# helmet_blinker_light_ACY_v0_1.net
KiCad netlist of a schematic drawn in EAGLE
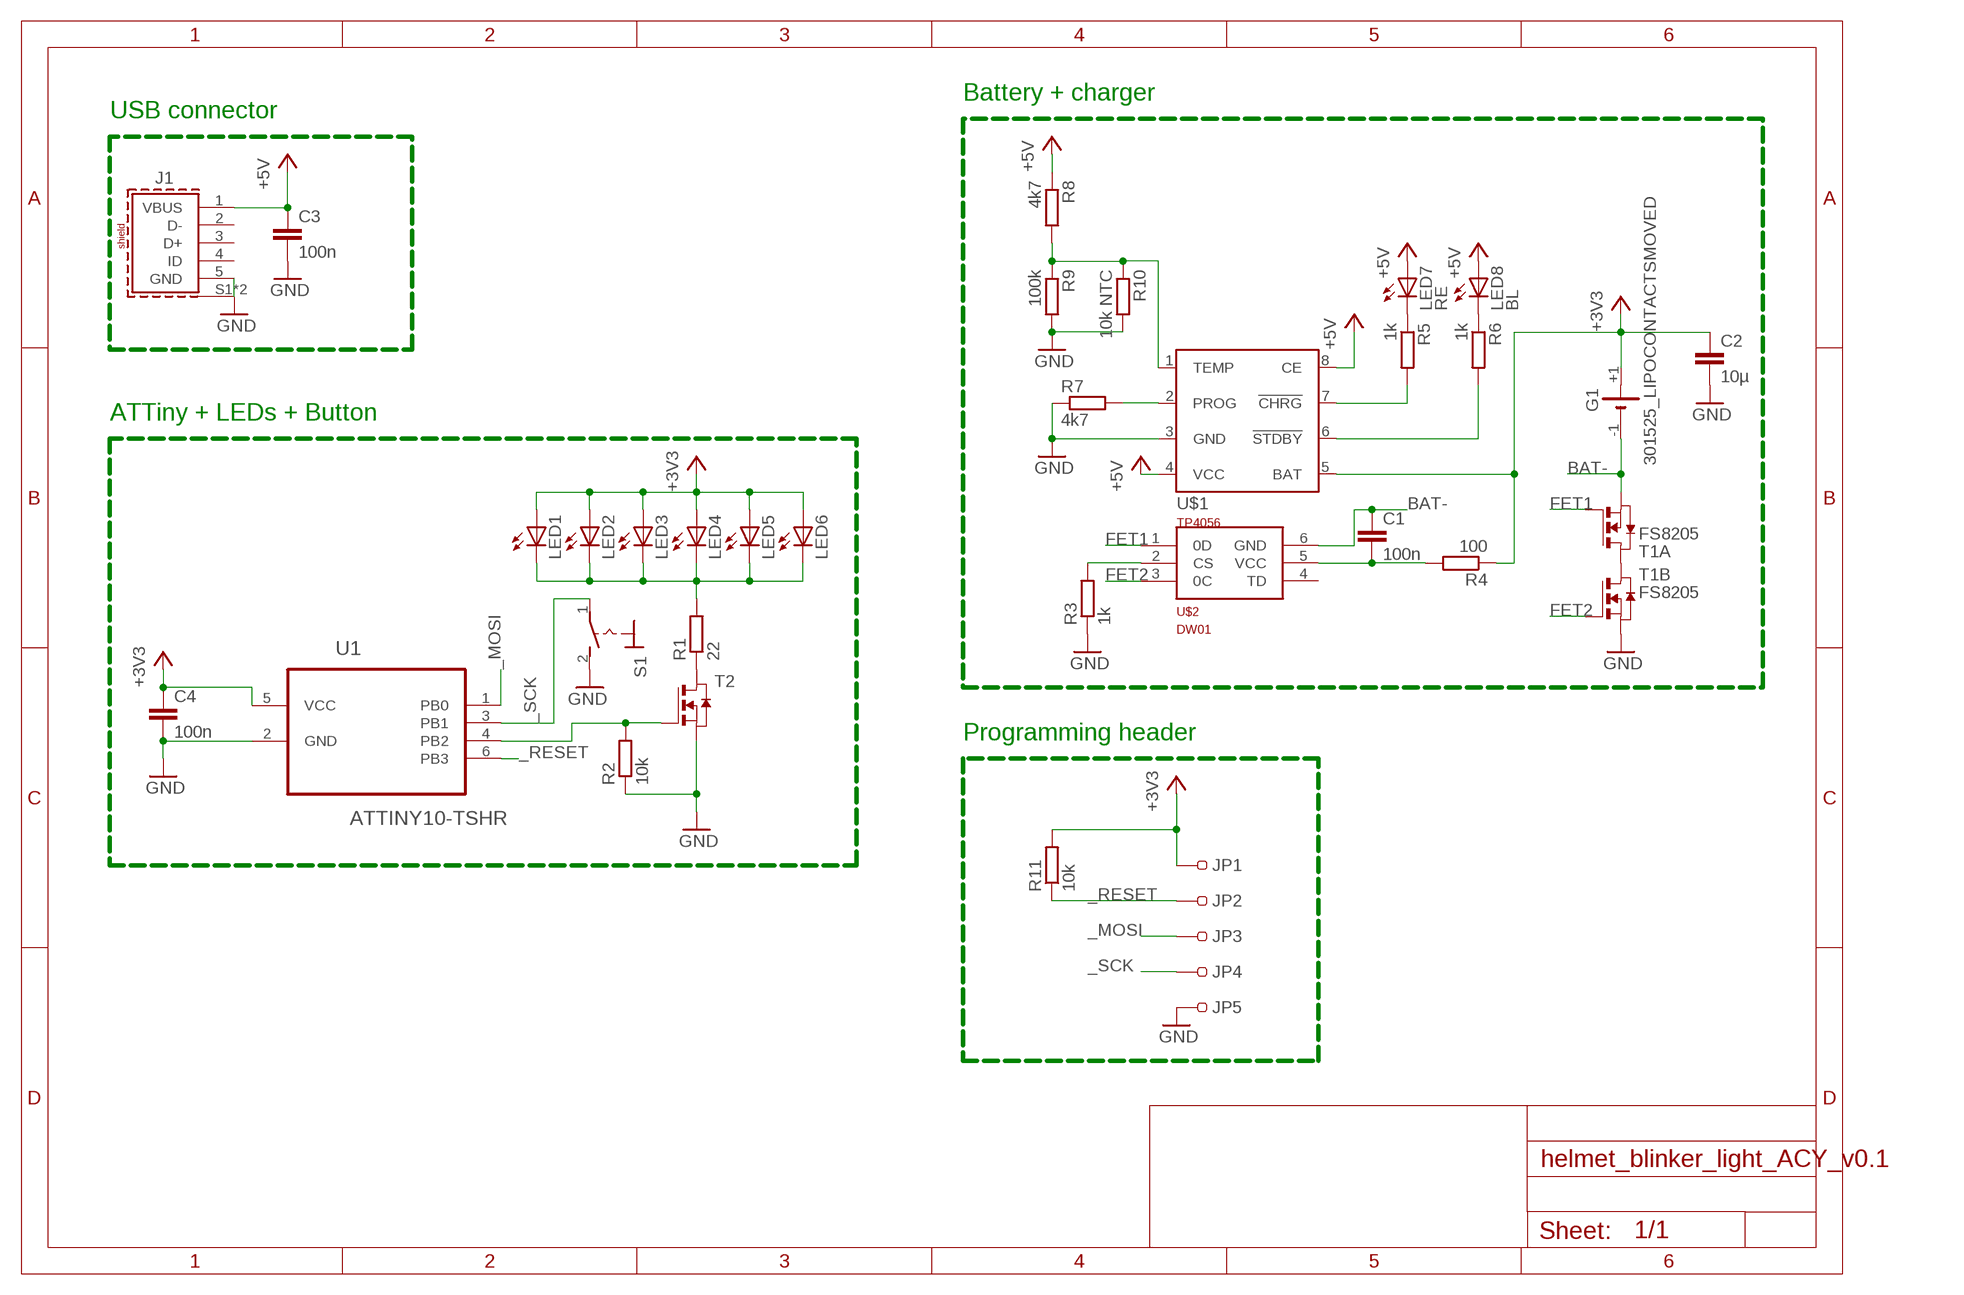
[diagram p0: schematic, sheet 1]

(export (version "E")
  (design (tool "Eeschema 10.0.6"))
  (components
    (comp (ref "C1")
      (value "100n")
      (footprint "eagle-import:C0402K")
      (libsource (lib "eagle-import") (part "C-EUC0402K"))
    )
    (comp (ref "C2")
      (value "10µ")
      (footprint "eagle-import:C0805K")
      (libsource (lib "eagle-import") (part "C-EUC0805K"))
    )
    (comp (ref "C3")
      (value "100n")
      (footprint "eagle-import:C0402K")
      (libsource (lib "eagle-import") (part "C-EUC0402K"))
    )
    (comp (ref "C4")
      (value "100n")
      (footprint "eagle-import:C0402K")
      (libsource (lib "eagle-import") (part "C-EUC0402K"))
    )
    (comp (ref "G1")
      (value "301525_LIPOCONTACTSMOVED")
      (footprint "eagle-import:301525_LIPO_CONTACTSMOVED")
      (libsource (lib "eagle-import") (part "301525_LIPOCONTACTSMOVED"))
    )
    (comp (ref "J1")
      (value "614105150621")
      (footprint "eagle-import:614105150621")
      (libsource (lib "eagle-import") (part "614105150621"))
    )
    (comp (ref "JP1")
      (value "0.7MM_POGO-PINS")
      (footprint "eagle-import:0.7MM_POGO-PINS")
      (libsource (lib "eagle-import") (part "0.7MM_POGO-PINS"))
    )
    (comp (ref "JP2")
      (value "0.7MM_POGO-PINS")
      (footprint "eagle-import:0.7MM_POGO-PINS")
      (libsource (lib "eagle-import") (part "0.7MM_POGO-PINS"))
    )
    (comp (ref "JP3")
      (value "0.7MM_POGO-PINS")
      (footprint "eagle-import:0.7MM_POGO-PINS")
      (libsource (lib "eagle-import") (part "0.7MM_POGO-PINS"))
    )
    (comp (ref "JP4")
      (value "0.7MM_POGO-PINS")
      (footprint "eagle-import:0.7MM_POGO-PINS")
      (libsource (lib "eagle-import") (part "0.7MM_POGO-PINS"))
    )
    (comp (ref "JP5")
      (value "0.7MM_POGO-PINS")
      (footprint "eagle-import:0.7MM_POGO-PINS")
      (libsource (lib "eagle-import") (part "0.7MM_POGO-PINS"))
    )
    (comp (ref "LED1")
      (value "LEDCHIPLED_0805")
      (footprint "eagle-import:CHIPLED_0805")
      (libsource (lib "eagle-import") (part "LEDCHIPLED_0805"))
    )
    (comp (ref "LED2")
      (value "LEDCHIPLED_0805")
      (footprint "eagle-import:CHIPLED_0805")
      (libsource (lib "eagle-import") (part "LEDCHIPLED_0805"))
    )
    (comp (ref "LED3")
      (value "LEDCHIPLED_0805")
      (footprint "eagle-import:CHIPLED_0805")
      (libsource (lib "eagle-import") (part "LEDCHIPLED_0805"))
    )
    (comp (ref "LED4")
      (value "LEDCHIPLED_0805")
      (footprint "eagle-import:CHIPLED_0805")
      (libsource (lib "eagle-import") (part "LEDCHIPLED_0805"))
    )
    (comp (ref "LED5")
      (value "LEDCHIPLED_0805")
      (footprint "eagle-import:CHIPLED_0805")
      (libsource (lib "eagle-import") (part "LEDCHIPLED_0805"))
    )
    (comp (ref "LED6")
      (value "LEDCHIPLED_0805")
      (footprint "eagle-import:CHIPLED_0805")
      (libsource (lib "eagle-import") (part "LEDCHIPLED_0805"))
    )
    (comp (ref "LED7")
      (value "RE")
      (footprint "eagle-import:CHIPLED_0603")
      (libsource (lib "eagle-import") (part "LEDCHIPLED_0603"))
    )
    (comp (ref "LED8")
      (value "BL")
      (footprint "eagle-import:CHIPLED_0603")
      (libsource (lib "eagle-import") (part "LEDCHIPLED_0603"))
    )
    (comp (ref "R1")
      (value "22")
      (footprint "eagle-import:R0805")
      (libsource (lib "eagle-import") (part "R-EU_R0805"))
    )
    (comp (ref "R2")
      (value "10k")
      (footprint "eagle-import:R0402")
      (libsource (lib "eagle-import") (part "R-EU_R0402"))
    )
    (comp (ref "R3")
      (value "1k")
      (footprint "eagle-import:R0402")
      (libsource (lib "eagle-import") (part "R-EU_R0402"))
    )
    (comp (ref "R4")
      (value "100")
      (footprint "eagle-import:R0402")
      (libsource (lib "eagle-import") (part "R-EU_R0402"))
    )
    (comp (ref "R5")
      (value "1k")
      (footprint "eagle-import:R0402")
      (libsource (lib "eagle-import") (part "R-EU_R0402"))
    )
    (comp (ref "R6")
      (value "1k")
      (footprint "eagle-import:R0402")
      (libsource (lib "eagle-import") (part "R-EU_R0402"))
    )
    (comp (ref "R7")
      (value "4k7")
      (footprint "eagle-import:R0402")
      (libsource (lib "eagle-import") (part "R-EU_R0402"))
    )
    (comp (ref "R8")
      (value "4k7")
      (footprint "eagle-import:R0402")
      (libsource (lib "eagle-import") (part "R-EU_R0402"))
    )
    (comp (ref "R9")
      (value "100k")
      (footprint "eagle-import:R0402")
      (libsource (lib "eagle-import") (part "R-EU_R0402"))
    )
    (comp (ref "R10")
      (value "10k NTC")
      (footprint "eagle-import:R0805")
      (libsource (lib "eagle-import") (part "R-EU_R0805"))
    )
    (comp (ref "R11")
      (value "10k")
      (footprint "eagle-import:R0402")
      (libsource (lib "eagle-import") (part "R-EU_R0402"))
    )
    (comp (ref "S1")
      (value "TS-1088")
      (footprint "eagle-import:TS-1088")
      (libsource (lib "eagle-import") (part "TS-1088"))
    )
    (comp (ref "T1")
      (value "FS8205")
      (footprint "eagle-import:TSSOP-8")
      (libsource (lib "eagle-import") (part "DMN3024LSD"))
    )
    (comp (ref "T2")
      (value "NMOSSOT23")
      (footprint "eagle-import:SOT-23")
      (libsource (lib "eagle-import") (part "NMOSSOT23"))
    )
    (comp (ref "U$1")
      (value "TP4056ESOP")
      (footprint "eagle-import:ESOP23-8")
      (libsource (lib "eagle-import") (part "TP4056ESOP"))
    )
    (comp (ref "U$2")
      (value "DW01")
      (footprint "eagle-import:SOT23-6")
      (libsource (lib "eagle-import") (part "DW01"))
    )
    (comp (ref "U1")
      (value "ATTINY10-TSHR")
      (footprint "eagle-import:SOT95P280X145-6N")
      (libsource (lib "eagle-import") (part "ATTINY10-TSHR"))
    )
  )
  (nets
    (net (code "1") (name "+3V3") (class "Default")
      (node (ref "C2") (pin "1") (pinfunction "1_1") (pintype "passive"))
      (node (ref "C4") (pin "1") (pinfunction "1_1") (pintype "passive"))
      (node (ref "G1") (pin "+1") (pinfunction "+_+1") (pintype "passive"))
      (node (ref "JP1") (pin "1") (pinfunction "1_1") (pintype "passive"))
      (node (ref "LED1") (pin "A") (pinfunction "A_A") (pintype "passive"))
      (node (ref "LED2") (pin "A") (pinfunction "A_A") (pintype "passive"))
      (node (ref "LED3") (pin "A") (pinfunction "A_A") (pintype "passive"))
      (node (ref "LED4") (pin "A") (pinfunction "A_A") (pintype "passive"))
      (node (ref "LED5") (pin "A") (pinfunction "A_A") (pintype "passive"))
      (node (ref "LED6") (pin "A") (pinfunction "A_A") (pintype "passive"))
      (node (ref "R11") (pin "2") (pinfunction "2_2") (pintype "passive"))
      (node (ref "R4") (pin "1") (pinfunction "1_1") (pintype "passive"))
      (node (ref "U$1") (pin "5") (pinfunction "BAT_5") (pintype "bidirectional"))
      (node (ref "U1") (pin "5") (pinfunction "VCC_5") (pintype "power_in"))
    )
    (net (code "2") (name "+5V") (class "Default")
      (node (ref "C3") (pin "1") (pinfunction "1_1") (pintype "passive"))
      (node (ref "J1") (pin "1") (pinfunction "VBUS_1") (pintype "passive"))
      (node (ref "LED7") (pin "A") (pinfunction "A_A") (pintype "passive"))
      (node (ref "LED8") (pin "A") (pinfunction "A_A") (pintype "passive"))
      (node (ref "R8") (pin "1") (pinfunction "1_1") (pintype "passive"))
      (node (ref "U$1") (pin "4") (pinfunction "VCC_4") (pintype "bidirectional"))
      (node (ref "U$1") (pin "8") (pinfunction "CE_8") (pintype "bidirectional"))
    )
    (net (code "3") (name "/BAT-") (class "Default")
      (node (ref "C1") (pin "1") (pinfunction "1_1") (pintype "passive"))
      (node (ref "G1") (pin "-1") (pinfunction "-_-1") (pintype "passive"))
      (node (ref "T1") (pin "2") (pinfunction "S_2") (pintype "passive"))
      (node (ref "T1") (pin "3") (pinfunction "S_3") (pintype "passive"))
      (node (ref "U$2") (pin "6") (pinfunction "GND_6") (pintype "bidirectional"))
    )
    (net (code "4") (name "/FET1") (class "Default")
      (node (ref "T1") (pin "4") (pinfunction "G_4") (pintype "passive"))
      (node (ref "U$2") (pin "1") (pinfunction "0D_1") (pintype "bidirectional"))
    )
    (net (code "5") (name "/FET2") (class "Default")
      (node (ref "T1") (pin "5") (pinfunction "G_5") (pintype "passive"))
      (node (ref "U$2") (pin "3") (pinfunction "0C_3") (pintype "bidirectional"))
    )
    (net (code "6") (name "/_MOSI") (class "Default")
      (node (ref "JP3") (pin "1") (pinfunction "1_1") (pintype "passive"))
      (node (ref "U1") (pin "1") (pinfunction "PB0_1") (pintype "bidirectional"))
    )
    (net (code "7") (name "/_RESET") (class "Default")
      (node (ref "JP2") (pin "1") (pinfunction "1_1") (pintype "passive"))
      (node (ref "R11") (pin "1") (pinfunction "1_1") (pintype "passive"))
      (node (ref "U1") (pin "6") (pinfunction "PB3_6") (pintype "bidirectional"))
    )
    (net (code "8") (name "/_SCK") (class "Default")
      (node (ref "JP4") (pin "1") (pinfunction "1_1") (pintype "passive"))
      (node (ref "S1") (pin "1") (pinfunction "P_1") (pintype "passive"))
      (node (ref "U1") (pin "3") (pinfunction "PB1_3") (pintype "bidirectional"))
    )
    (net (code "9") (name "GND") (class "Default")
      (node (ref "C2") (pin "2") (pinfunction "2_2") (pintype "passive"))
      (node (ref "C3") (pin "2") (pinfunction "2_2") (pintype "passive"))
      (node (ref "C4") (pin "2") (pinfunction "2_2") (pintype "passive"))
      (node (ref "J1") (pin "5") (pinfunction "GND_5") (pintype "passive"))
      (node (ref "J1") (pin "S1") (pinfunction "SHIELD_S1") (pintype "passive"))
      (node (ref "J1") (pin "S2") (pinfunction "SHIELD_S2") (pintype "passive"))
      (node (ref "JP5") (pin "1") (pinfunction "1_1") (pintype "passive"))
      (node (ref "R10") (pin "2") (pinfunction "2_2") (pintype "passive"))
      (node (ref "R2") (pin "1") (pinfunction "1_1") (pintype "passive"))
      (node (ref "R3") (pin "1") (pinfunction "1_1") (pintype "passive"))
      (node (ref "R7") (pin "1") (pinfunction "1_1") (pintype "passive"))
      (node (ref "R9") (pin "2") (pinfunction "2_2") (pintype "passive"))
      (node (ref "S1") (pin "2") (pinfunction "S_2") (pintype "passive"))
      (node (ref "T1") (pin "6") (pinfunction "S_6") (pintype "passive"))
      (node (ref "T1") (pin "7") (pinfunction "S_7") (pintype "passive"))
      (node (ref "T2") (pin "2") (pinfunction "S_2") (pintype "passive"))
      (node (ref "U$1") (pin "3") (pinfunction "GND_3") (pintype "bidirectional"))
      (node (ref "U1") (pin "2") (pinfunction "GND_2") (pintype "passive"))
    )
    (net (code "10") (name "Net-(LED1-PadC)") (class "Default")
      (node (ref "LED1") (pin "C") (pinfunction "C_C") (pintype "passive"))
      (node (ref "LED2") (pin "C") (pinfunction "C_C") (pintype "passive"))
      (node (ref "LED3") (pin "C") (pinfunction "C_C") (pintype "passive"))
      (node (ref "LED4") (pin "C") (pinfunction "C_C") (pintype "passive"))
      (node (ref "LED5") (pin "C") (pinfunction "C_C") (pintype "passive"))
      (node (ref "LED6") (pin "C") (pinfunction "C_C") (pintype "passive"))
      (node (ref "R1") (pin "2") (pinfunction "2_2") (pintype "passive"))
    )
    (net (code "11") (name "Net-(LED7-PadC)") (class "Default")
      (node (ref "LED7") (pin "C") (pinfunction "C_C") (pintype "passive"))
      (node (ref "R5") (pin "1") (pinfunction "1_1") (pintype "passive"))
    )
    (net (code "12") (name "Net-(LED8-PadC)") (class "Default")
      (node (ref "LED8") (pin "C") (pinfunction "C_C") (pintype "passive"))
      (node (ref "R6") (pin "1") (pinfunction "1_1") (pintype "passive"))
    )
    (net (code "13") (name "Net-(T1A-D)") (class "Default")
      (node (ref "T1") (pin "1") (pinfunction "D_1") (pintype "passive"))
      (node (ref "T1") (pin "8") (pinfunction "D_8") (pintype "passive"))
    )
    (net (code "14") (name "Net-(T2-D)") (class "Default")
      (node (ref "R1") (pin "1") (pinfunction "1_1") (pintype "passive"))
      (node (ref "T2") (pin "1") (pinfunction "D_1") (pintype "passive"))
    )
    (net (code "15") (name "Net-(T2-G)") (class "Default")
      (node (ref "R2") (pin "2") (pinfunction "2_2") (pintype "passive"))
      (node (ref "T2") (pin "3") (pinfunction "G_3") (pintype "passive"))
      (node (ref "U1") (pin "4") (pinfunction "PB2_4") (pintype "bidirectional"))
    )
    (net (code "16") (name "Net-(U$1-PROG)") (class "Default")
      (node (ref "R7") (pin "2") (pinfunction "2_2") (pintype "passive"))
      (node (ref "U$1") (pin "2") (pinfunction "PROG_2") (pintype "bidirectional"))
    )
    (net (code "17") (name "Net-(U$1-TEMP)") (class "Default")
      (node (ref "R10") (pin "1") (pinfunction "1_1") (pintype "passive"))
      (node (ref "R8") (pin "2") (pinfunction "2_2") (pintype "passive"))
      (node (ref "R9") (pin "1") (pinfunction "1_1") (pintype "passive"))
      (node (ref "U$1") (pin "1") (pinfunction "TEMP_1") (pintype "bidirectional"))
    )
    (net (code "18") (name "Net-(U$1-~{CHRG})") (class "Default")
      (node (ref "R5") (pin "2") (pinfunction "2_2") (pintype "passive"))
      (node (ref "U$1") (pin "7") (pinfunction "~{CHRG}_7") (pintype "bidirectional"))
    )
    (net (code "19") (name "Net-(U$1-~{STDBY})") (class "Default")
      (node (ref "R6") (pin "2") (pinfunction "2_2") (pintype "passive"))
      (node (ref "U$1") (pin "6") (pinfunction "~{STDBY}_6") (pintype "bidirectional"))
    )
    (net (code "20") (name "Net-(U$2-CS)") (class "Default")
      (node (ref "R3") (pin "2") (pinfunction "2_2") (pintype "passive"))
      (node (ref "U$2") (pin "2") (pinfunction "CS_2") (pintype "bidirectional"))
    )
    (net (code "21") (name "Net-(U$2-VCC)") (class "Default")
      (node (ref "C1") (pin "2") (pinfunction "2_2") (pintype "passive"))
      (node (ref "R4") (pin "2") (pinfunction "2_2") (pintype "passive"))
      (node (ref "U$2") (pin "5") (pinfunction "VCC_5") (pintype "bidirectional"))
    )
    (net (code "22") (name "unconnected-(J1-D+-Pad3)") (class "Default")
      (node (ref "J1") (pin "3") (pinfunction "D+_3") (pintype "passive"))
    )
    (net (code "23") (name "unconnected-(J1-D--Pad2)") (class "Default")
      (node (ref "J1") (pin "2") (pinfunction "D-_2") (pintype "passive"))
    )
    (net (code "24") (name "unconnected-(J1-ID-Pad4)") (class "Default")
      (node (ref "J1") (pin "4") (pinfunction "ID_4") (pintype "passive"))
    )
    (net (code "25") (name "unconnected-(U$2-TD-Pad4)") (class "Default")
      (node (ref "U$2") (pin "4") (pinfunction "TD_4") (pintype "bidirectional"))
    )
  )
)
